# clocking.net
KiCad netlist of a schematic drawn in Altium Designer
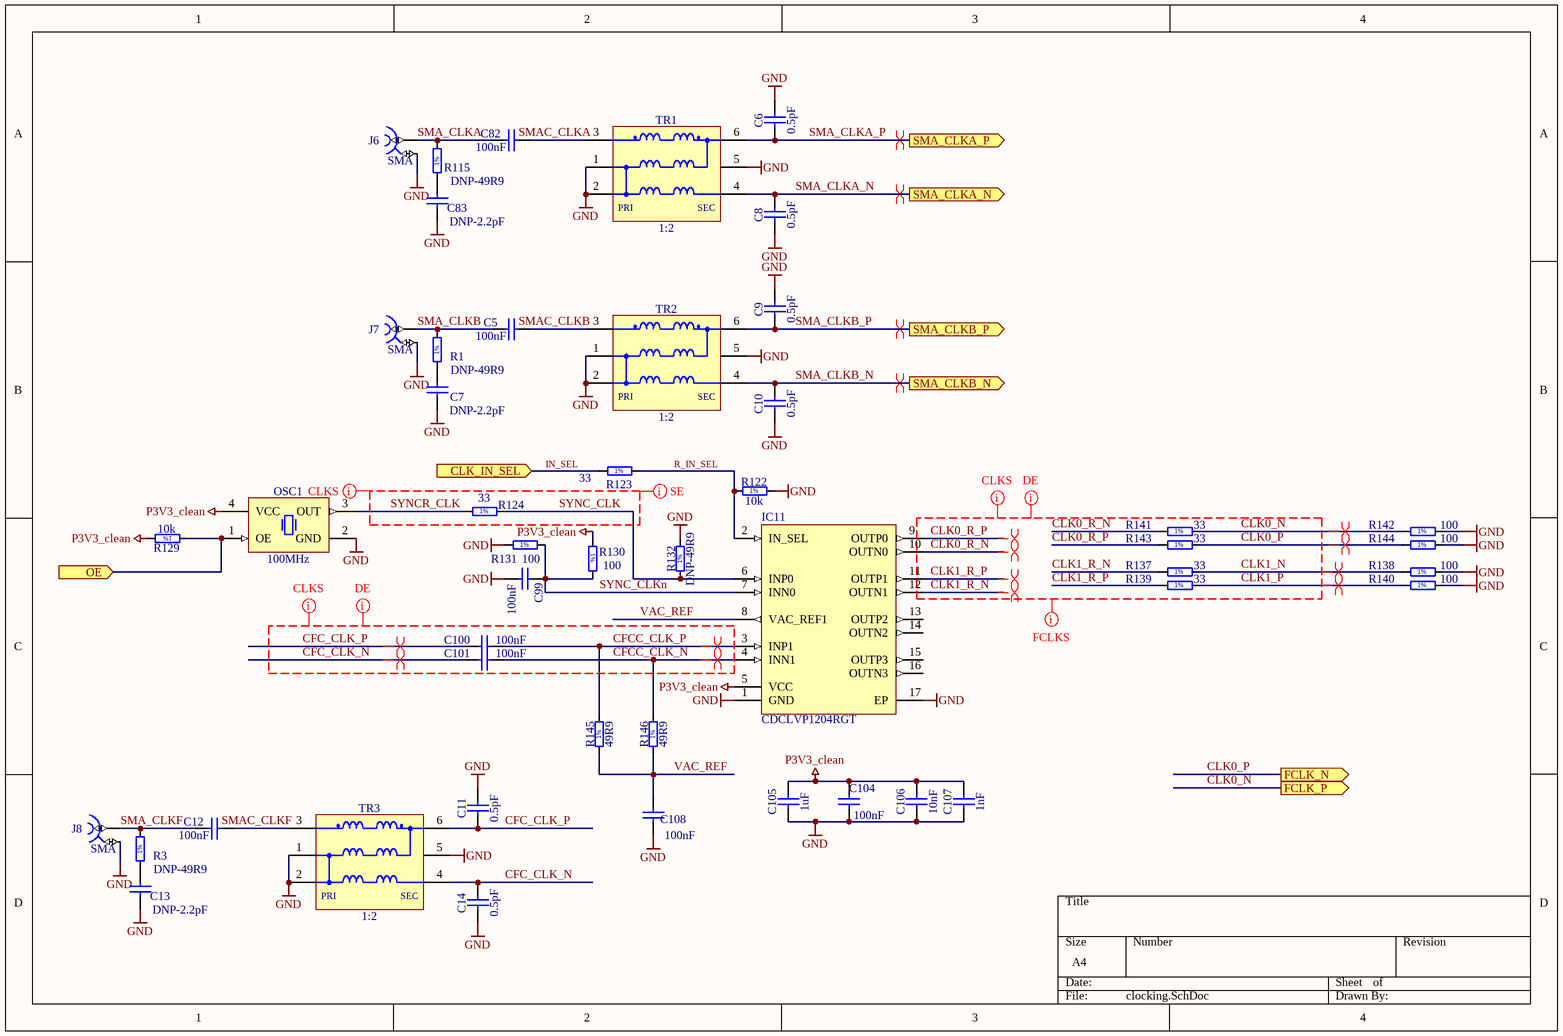
[diagram p0: clocking.SchDoc]

(export (version "E")
  (design (tool "Eeschema 10.0.6"))
  (components
    (comp (ref "C5")
      (value "100nF")
      (footprint "CAPC1005X55N")
      (description "Non-polarised capacitor")
      (fields
        (field (name "PART NUMBER") "CC0402_100NF_16V_10%_X5R")
        (field (name "VOLTAGE") "16V")
        (field (name "AUTHOR") "CERN DEM JLC")
      )
      (libsource (lib "Capacitors") (part "Capacitor - non polarized"))
    )
    (comp (ref "C6")
      (value "0.5pF")
      (footprint "CAPC1005X50N")
      (description "Non-polarised capacitor")
      (fields
        (field (name "PART NUMBER") "CC0402_0.5PF_25V_0.05PF_AVX_04023J0R5ABSTR")
        (field (name "VOLTAGE") "25V")
        (field (name "AUTHOR") "CERN DEM JLC")
      )
      (libsource (lib "Capacitors") (part "Capacitor - non polarized"))
    )
    (comp (ref "C7")
      (value "DNP-2.2pF")
      (footprint "CAPC1005X55N")
      (description "Non-polarised capacitor")
      (fields
        (field (name "PART NUMBER") "CC0402_2.2PF_50V_0.25PF_NP0")
        (field (name "VOLTAGE") "50V")
        (field (name "AUTHOR") "CERN DEM JLC")
      )
      (libsource (lib "Capacitors") (part "Capacitor - non polarized"))
    )
    (comp (ref "C8")
      (value "0.5pF")
      (footprint "CAPC1005X50N")
      (description "Non-polarised capacitor")
      (fields
        (field (name "PART NUMBER") "CC0402_0.5PF_25V_0.05PF_AVX_04023J0R5ABSTR")
        (field (name "VOLTAGE") "25V")
        (field (name "AUTHOR") "CERN DEM JLC")
      )
      (libsource (lib "Capacitors") (part "Capacitor - non polarized"))
    )
    (comp (ref "C9")
      (value "0.5pF")
      (footprint "CAPC1005X50N")
      (description "Non-polarised capacitor")
      (fields
        (field (name "PART NUMBER") "CC0402_0.5PF_25V_0.05PF_AVX_04023J0R5ABSTR")
        (field (name "VOLTAGE") "25V")
        (field (name "AUTHOR") "CERN DEM JLC")
      )
      (libsource (lib "Capacitors") (part "Capacitor - non polarized"))
    )
    (comp (ref "C10")
      (value "0.5pF")
      (footprint "CAPC1005X50N")
      (description "Non-polarised capacitor")
      (fields
        (field (name "PART NUMBER") "CC0402_0.5PF_25V_0.05PF_AVX_04023J0R5ABSTR")
        (field (name "VOLTAGE") "25V")
        (field (name "AUTHOR") "CERN DEM JLC")
      )
      (libsource (lib "Capacitors") (part "Capacitor - non polarized"))
    )
    (comp (ref "C11")
      (value "0.5pF")
      (footprint "CAPC1005X50N")
      (description "Non-polarised capacitor")
      (fields
        (field (name "PART NUMBER") "CC0402_0.5PF_25V_0.05PF_AVX_04023J0R5ABSTR")
        (field (name "VOLTAGE") "25V")
        (field (name "AUTHOR") "CERN DEM JLC")
      )
      (libsource (lib "Capacitors") (part "Capacitor - non polarized"))
    )
    (comp (ref "C12")
      (value "100nF")
      (footprint "CAPC1005X55N")
      (description "Non-polarised capacitor")
      (fields
        (field (name "PART NUMBER") "CC0402_100NF_16V_10%_X5R")
        (field (name "VOLTAGE") "16V")
        (field (name "AUTHOR") "CERN DEM JLC")
      )
      (libsource (lib "Capacitors") (part "Capacitor - non polarized"))
    )
    (comp (ref "C13")
      (value "DNP-2.2pF")
      (footprint "CAPC1005X55N")
      (description "Non-polarised capacitor")
      (fields
        (field (name "PART NUMBER") "CC0402_2.2PF_50V_0.25PF_NP0")
        (field (name "VOLTAGE") "50V")
        (field (name "AUTHOR") "CERN DEM JLC")
      )
      (libsource (lib "Capacitors") (part "Capacitor - non polarized"))
    )
    (comp (ref "C14")
      (value "0.5pF")
      (footprint "CAPC1005X50N")
      (description "Non-polarised capacitor")
      (fields
        (field (name "PART NUMBER") "CC0402_0.5PF_25V_0.05PF_AVX_04023J0R5ABSTR")
        (field (name "VOLTAGE") "25V")
        (field (name "AUTHOR") "CERN DEM JLC")
      )
      (libsource (lib "Capacitors") (part "Capacitor - non polarized"))
    )
    (comp (ref "C82")
      (value "100nF")
      (footprint "CAPC1005X55N")
      (description "Non-polarised capacitor")
      (fields
        (field (name "PART NUMBER") "CC0402_100NF_16V_10%_X5R")
        (field (name "VOLTAGE") "16V")
        (field (name "AUTHOR") "CERN DEM JLC")
      )
      (libsource (lib "Capacitors") (part "Capacitor - non polarized"))
    )
    (comp (ref "C83")
      (value "DNP-2.2pF")
      (footprint "CAPC1005X55N")
      (description "Non-polarised capacitor")
      (fields
        (field (name "PART NUMBER") "CC0402_2.2PF_50V_0.25PF_NP0")
        (field (name "VOLTAGE") "50V")
        (field (name "AUTHOR") "CERN DEM JLC")
      )
      (libsource (lib "Capacitors") (part "Capacitor - non polarized"))
    )
    (comp (ref "C99")
      (value "100nF")
      (footprint "CAPC0603X33N")
      (description "Non-polarised capacitor")
      (fields
        (field (name "PART NUMBER") "CC0201_100NF_6.3V_10%_X5R")
        (field (name "VOLTAGE") "6.3V")
        (field (name "AUTHOR") "CERN DEM JLC")
      )
      (libsource (lib "Capacitors") (part "Capacitor - non polarized"))
    )
    (comp (ref "C100")
      (value "100nF")
      (footprint "CAPC0603X33N")
      (description "Non-polarised capacitor")
      (fields
        (field (name "PART NUMBER") "CC0201_100NF_6.3V_10%_X5R")
        (field (name "VOLTAGE") "6.3V")
        (field (name "AUTHOR") "CERN DEM JLC")
      )
      (libsource (lib "Capacitors") (part "Capacitor - non polarized"))
    )
    (comp (ref "C101")
      (value "100nF")
      (footprint "CAPC0603X33N")
      (description "Non-polarised capacitor")
      (fields
        (field (name "PART NUMBER") "CC0201_100NF_6.3V_10%_X5R")
        (field (name "VOLTAGE") "6.3V")
        (field (name "AUTHOR") "CERN DEM JLC")
      )
      (libsource (lib "Capacitors") (part "Capacitor - non polarized"))
    )
    (comp (ref "C104")
      (value "100nF")
      (footprint "CAPC0603X33N")
      (description "Non-polarised capacitor")
      (fields
        (field (name "PART NUMBER") "CC0201_100NF_6.3V_10%_X5R")
        (field (name "VOLTAGE") "6.3V")
        (field (name "AUTHOR") "CERN DEM JLC")
      )
      (libsource (lib "Capacitors") (part "Capacitor - non polarized"))
    )
    (comp (ref "C105")
      (value "1uF")
      (footprint "CAPC1608X87N")
      (description "Non-polarised capacitor")
      (fields
        (field (name "PART NUMBER") "CC0603_1UF_25V_10%_X7R")
        (field (name "VOLTAGE") "25V")
        (field (name "AUTHOR") "CERN DEM JLC")
      )
      (libsource (lib "Capacitors") (part "Capacitor - non polarized"))
    )
    (comp (ref "C106")
      (value "10nF")
      (footprint "CAPC0603X33N")
      (description "Non-polarised capacitor")
      (fields
        (field (name "PART NUMBER") "CC0201_10NF_10V_10%_X5R")
        (field (name "VOLTAGE") "10V")
        (field (name "AUTHOR") "CERN DEM JLC")
      )
      (libsource (lib "Capacitors") (part "Capacitor - non polarized"))
    )
    (comp (ref "C107")
      (value "1nF")
      (footprint "CAPC0603X33N")
      (description "Non-polarised capacitor")
      (fields
        (field (name "PART NUMBER") "CC0201_1NF_16V_10%_X5R")
        (field (name "VOLTAGE") "16V")
        (field (name "AUTHOR") "CERN DEM JLC")
      )
      (libsource (lib "Capacitors") (part "Capacitor - non polarized"))
    )
    (comp (ref "C108")
      (value "100nF")
      (footprint "CAPC1005X55N")
      (description "Non-polarised capacitor")
      (fields
        (field (name "PART NUMBER") "CC0402_100NF_16V_10%_X5R")
        (field (name "VOLTAGE") "16V")
        (field (name "AUTHOR") "CERN DEM JLC")
      )
      (libsource (lib "Capacitors") (part "Capacitor - non polarized"))
    )
    (comp (ref "IC11")
      (value "CDCLVP1204RGT")
      (footprint "QFN50P300X300X100-17N-S165")
      (description "2:2 Low Additive Jitter LVPECL Buffer")
      (libsource (lib "TJ_LIB") (part "CDCLVP1204RGT"))
    )
    (comp (ref "J6")
      (value "SMA")
      (footprint "HUBER-SUHNER_85_SMA-50-0-101/111_NE")
      (fields
        (field (name "PART NUMBER") "HUBER-SUHNER_85_SMA-50-0-101/111_NE")
        (field (name "MANUFACTURER") "HUBER+SUHNER")
        (field (name "MANUFACTURER PART NUMBER") "85_SMA-50-0-101/111_NE")
        (field (name "AUTHOR") "CERN DEM JLC")
      )
      (libsource (lib "Connectors") (part "Coax_1Female_1Shield"))
    )
    (comp (ref "J7")
      (value "SMA")
      (footprint "HUBER-SUHNER_85_SMA-50-0-101/111_NE")
      (fields
        (field (name "PART NUMBER") "HUBER-SUHNER_85_SMA-50-0-101/111_NE")
        (field (name "MANUFACTURER") "HUBER+SUHNER")
        (field (name "MANUFACTURER PART NUMBER") "85_SMA-50-0-101/111_NE")
        (field (name "AUTHOR") "CERN DEM JLC")
      )
      (libsource (lib "Connectors") (part "Coax_1Female_1Shield"))
    )
    (comp (ref "J8")
      (value "SMA")
      (footprint "HUBER-SUHNER_85_SMA-50-0-101/111_NE")
      (fields
        (field (name "PART NUMBER") "HUBER-SUHNER_85_SMA-50-0-101/111_NE")
        (field (name "MANUFACTURER") "HUBER+SUHNER")
        (field (name "MANUFACTURER PART NUMBER") "85_SMA-50-0-101/111_NE")
        (field (name "AUTHOR") "CERN DEM JLC")
      )
      (libsource (lib "Connectors") (part "Coax_1Female_1Shield"))
    )
    (comp (ref "OSC1")
      (value "100MHz")
      (footprint "OSC_EPSON_SG-8002CA")
      (description "Oscillator 4 pins 1=OE 2=GND 3=OUT 4=VCC")
      (fields
        (field (name "PART NUMBER") "OSC_100MHZ_EPSON_SG-8002CAPCB100MHZ")
        (field (name "MANUFACTURER") "EPSON-TOYOCOM")
        (field (name "AUTHOR") "CERN DEM JLC")
      )
      (libsource (lib "ICs And Semiconductors") (part "Oscillator 1OE 2GND 3OUT 4VCC"))
    )
    (comp (ref "R1")
      (value "DNP-49R9")
      (footprint "RESC1005X40N")
      (description "Resistor - 1%")
      (fields
        (field (name "PART NUMBER") "R0402_49R9_1%_0.0625W_100PPM")
        (field (name "POWER") "0.0625W")
        (field (name "AUTHOR") "CERN DEM JLC")
      )
      (libsource (lib "Resistors") (part "Resistor - 1%"))
    )
    (comp (ref "R3")
      (value "DNP-49R9")
      (footprint "RESC1005X40N")
      (description "Resistor - 1%")
      (fields
        (field (name "PART NUMBER") "R0402_49R9_1%_0.0625W_100PPM")
        (field (name "POWER") "0.0625W")
        (field (name "AUTHOR") "CERN DEM JLC")
      )
      (libsource (lib "Resistors") (part "Resistor - 1%"))
    )
    (comp (ref "R115")
      (value "DNP-49R9")
      (footprint "RESC1005X40N")
      (description "Resistor - 1%")
      (fields
        (field (name "PART NUMBER") "R0402_49R9_1%_0.0625W_100PPM")
        (field (name "POWER") "0.0625W")
        (field (name "AUTHOR") "CERN DEM JLC")
      )
      (libsource (lib "Resistors") (part "Resistor - 1%"))
    )
    (comp (ref "R122")
      (value "10k")
      (footprint "RESC1005X40N")
      (description "Resistor - 1%")
      (fields
        (field (name "PART NUMBER") "R0402_10K_1%_0.0625W_100PPM")
        (field (name "POWER") "0.0625W")
        (field (name "AUTHOR") "CERN DEM JLC")
      )
      (libsource (lib "Resistors") (part "Resistor - 1%"))
    )
    (comp (ref "R123")
      (value "33")
      (footprint "RESC1005X40N")
      (description "Resistor - 1%")
      (fields
        (field (name "PART NUMBER") "R0402_33R_1%_0.0625W_100PPM")
        (field (name "POWER") "0.0625W")
        (field (name "AUTHOR") "CERN DEM JLC")
      )
      (libsource (lib "Resistors") (part "Resistor - 1%"))
    )
    (comp (ref "R124")
      (value "33")
      (footprint "RESC1005X40N")
      (description "Resistor - 1%")
      (fields
        (field (name "PART NUMBER") "R0402_33R_1%_0.0625W_100PPM")
        (field (name "POWER") "0.0625W")
        (field (name "AUTHOR") "CERN DEM JLC")
      )
      (libsource (lib "Resistors") (part "Resistor - 1%"))
    )
    (comp (ref "R129")
      (value "10k")
      (footprint "RESC1005X40N")
      (description "Resistor - 1%")
      (fields
        (field (name "PART NUMBER") "R0402_10K_1%_0.0625W_100PPM")
        (field (name "POWER") "0.0625W")
        (field (name "AUTHOR") "CERN DEM JLC")
      )
      (libsource (lib "Resistors") (part "Resistor - 1%"))
    )
    (comp (ref "R130")
      (value "100")
      (footprint "RESC1005X40N")
      (description "Resistor - 1%")
      (fields
        (field (name "PART NUMBER") "R0402_100R_1%_0.0625W_100PPM")
        (field (name "POWER") "0.0625W")
        (field (name "AUTHOR") "CERN DEM JLC")
      )
      (libsource (lib "Resistors") (part "Resistor - 1%"))
    )
    (comp (ref "R131")
      (value "100")
      (footprint "RESC1005X40N")
      (description "Resistor - 1%")
      (fields
        (field (name "PART NUMBER") "R0402_100R_1%_0.0625W_100PPM")
        (field (name "POWER") "0.0625W")
        (field (name "AUTHOR") "CERN DEM JLC")
      )
      (libsource (lib "Resistors") (part "Resistor - 1%"))
    )
    (comp (ref "R132")
      (value "DNP-49R9")
      (footprint "RESC1005X40N")
      (description "Resistor - 1%")
      (fields
        (field (name "PART NUMBER") "R0402_49R9_1%_0.0625W_100PPM")
        (field (name "POWER") "0.0625W")
        (field (name "AUTHOR") "CERN DEM JLC")
      )
      (libsource (lib "Resistors") (part "Resistor - 1%"))
    )
    (comp (ref "R137")
      (value "33")
      (footprint "RESC1005X40N")
      (description "Resistor - 1%")
      (fields
        (field (name "PART NUMBER") "R0402_33R_1%_0.0625W_100PPM")
        (field (name "POWER") "0.0625W")
        (field (name "AUTHOR") "CERN DEM JLC")
      )
      (libsource (lib "Resistors") (part "Resistor - 1%"))
    )
    (comp (ref "R138")
      (value "100")
      (footprint "RESC1005X40N")
      (description "Resistor - 1%")
      (fields
        (field (name "PART NUMBER") "R0402_100R_1%_0.0625W_100PPM")
        (field (name "POWER") "0.0625W")
        (field (name "AUTHOR") "CERN DEM JLC")
      )
      (libsource (lib "Resistors") (part "Resistor - 1%"))
    )
    (comp (ref "R139")
      (value "33")
      (footprint "RESC1005X40N")
      (description "Resistor - 1%")
      (fields
        (field (name "PART NUMBER") "R0402_33R_1%_0.0625W_100PPM")
        (field (name "POWER") "0.0625W")
        (field (name "AUTHOR") "CERN DEM JLC")
      )
      (libsource (lib "Resistors") (part "Resistor - 1%"))
    )
    (comp (ref "R140")
      (value "100")
      (footprint "RESC1005X40N")
      (description "Resistor - 1%")
      (fields
        (field (name "PART NUMBER") "R0402_100R_1%_0.0625W_100PPM")
        (field (name "POWER") "0.0625W")
        (field (name "AUTHOR") "CERN DEM JLC")
      )
      (libsource (lib "Resistors") (part "Resistor - 1%"))
    )
    (comp (ref "R141")
      (value "33")
      (footprint "RESC1005X40N")
      (description "Resistor - 1%")
      (fields
        (field (name "PART NUMBER") "R0402_33R_1%_0.0625W_100PPM")
        (field (name "POWER") "0.0625W")
        (field (name "AUTHOR") "CERN DEM JLC")
      )
      (libsource (lib "Resistors") (part "Resistor - 1%"))
    )
    (comp (ref "R142")
      (value "100")
      (footprint "RESC1005X40N")
      (description "Resistor - 1%")
      (fields
        (field (name "PART NUMBER") "R0402_100R_1%_0.0625W_100PPM")
        (field (name "POWER") "0.0625W")
        (field (name "AUTHOR") "CERN DEM JLC")
      )
      (libsource (lib "Resistors") (part "Resistor - 1%"))
    )
    (comp (ref "R143")
      (value "33")
      (footprint "RESC1005X40N")
      (description "Resistor - 1%")
      (fields
        (field (name "PART NUMBER") "R0402_33R_1%_0.0625W_100PPM")
        (field (name "POWER") "0.0625W")
        (field (name "AUTHOR") "CERN DEM JLC")
      )
      (libsource (lib "Resistors") (part "Resistor - 1%"))
    )
    (comp (ref "R144")
      (value "100")
      (footprint "RESC1005X40N")
      (description "Resistor - 1%")
      (fields
        (field (name "PART NUMBER") "R0402_100R_1%_0.0625W_100PPM")
        (field (name "POWER") "0.0625W")
        (field (name "AUTHOR") "CERN DEM JLC")
      )
      (libsource (lib "Resistors") (part "Resistor - 1%"))
    )
    (comp (ref "R145")
      (value "49R9")
      (footprint "RESC1005X40N")
      (description "Resistor - 1%")
      (fields
        (field (name "PART NUMBER") "R0402_49R9_1%_0.0625W_100PPM")
        (field (name "POWER") "0.0625W")
        (field (name "AUTHOR") "CERN DEM JLC")
      )
      (libsource (lib "Resistors") (part "Resistor - 1%"))
    )
    (comp (ref "R146")
      (value "49R9")
      (footprint "RESC1005X40N")
      (description "Resistor - 1%")
      (fields
        (field (name "PART NUMBER") "R0402_49R9_1%_0.0625W_100PPM")
        (field (name "POWER") "0.0625W")
        (field (name "AUTHOR") "CERN DEM JLC")
      )
      (libsource (lib "Resistors") (part "Resistor - 1%"))
    )
    (comp (ref "TR1")
      (value "1:2")
      (footprint "XFMR_MINI-CIRCUITS_DB1627")
      (description "50 OHMS 10 to 4000 MHz RF Transformer")
      (fields
        (field (name "PART NUMBER") "XFMR_MINI-CIRCUITS_TCM2-43X+")
        (field (name "POWER") "0.4W")
        (field (name "AUTHOR") "CERN DEM BC")
      )
      (libsource (lib "Inductors & Transformers") (part "XFMR_MINI-CIRCUITS_TCM2-43X"))
    )
    (comp (ref "TR2")
      (value "1:2")
      (footprint "XFMR_MINI-CIRCUITS_DB1627")
      (description "50 OHMS 10 to 4000 MHz RF Transformer")
      (fields
        (field (name "PART NUMBER") "XFMR_MINI-CIRCUITS_TCM2-43X+")
        (field (name "POWER") "0.4W")
        (field (name "AUTHOR") "CERN DEM BC")
      )
      (libsource (lib "Inductors & Transformers") (part "XFMR_MINI-CIRCUITS_TCM2-43X"))
    )
    (comp (ref "TR3")
      (value "1:2")
      (footprint "XFMR_MINI-CIRCUITS_DB1627")
      (description "50 OHMS 10 to 4000 MHz RF Transformer")
      (fields
        (field (name "PART NUMBER") "XFMR_MINI-CIRCUITS_TCM2-43X+")
        (field (name "POWER") "0.4W")
        (field (name "AUTHOR") "CERN DEM BC")
      )
      (libsource (lib "Inductors & Transformers") (part "XFMR_MINI-CIRCUITS_TCM2-43X"))
    )
  )
  (nets
    (net (code "1") (name "/CFCC_CLK_N") (class "Default")
      (node (ref "C101") (pin "1") (pinfunction "1_1") (pintype "passive"))
      (node (ref "IC11") (pin "4") (pinfunction "INN1_4") (pintype "input"))
      (node (ref "R146") (pin "2") (pinfunction "2_2") (pintype "passive"))
    )
    (net (code "2") (name "/CFCC_CLK_P") (class "Default")
      (node (ref "C100") (pin "1") (pinfunction "1_1") (pintype "passive"))
      (node (ref "IC11") (pin "3") (pinfunction "INP1_3") (pintype "input"))
      (node (ref "R145") (pin "2") (pinfunction "2_2") (pintype "passive"))
    )
    (net (code "3") (name "/CFC_CLK_N") (class "Default")
      (node (ref "C101") (pin "2") (pinfunction "2_2") (pintype "passive"))
      (node (ref "C14") (pin "2") (pinfunction "2_2") (pintype "passive"))
      (node (ref "TR3") (pin "4") (pinfunction "S1_4") (pintype "passive"))
    )
    (net (code "4") (name "/CFC_CLK_P") (class "Default")
      (node (ref "C100") (pin "2") (pinfunction "2_2") (pintype "passive"))
      (node (ref "C11") (pin "1") (pinfunction "1_1") (pintype "passive"))
      (node (ref "TR3") (pin "6") (pinfunction "S1_6") (pintype "passive"))
    )
    (net (code "5") (name "/CLK0_N") (class "Default")
      (node (ref "R141") (pin "2") (pinfunction "2_2") (pintype "passive"))
      (node (ref "R142") (pin "1") (pinfunction "1_1") (pintype "passive"))
    )
    (net (code "6") (name "/CLK0_P") (class "Default")
      (node (ref "R143") (pin "2") (pinfunction "2_2") (pintype "passive"))
      (node (ref "R144") (pin "1") (pinfunction "1_1") (pintype "passive"))
    )
    (net (code "7") (name "/CLK0_R_N") (class "Default")
      (node (ref "IC11") (pin "10") (pinfunction "OUTN0_10") (pintype "output"))
      (node (ref "R141") (pin "1") (pinfunction "1_1") (pintype "passive"))
    )
    (net (code "8") (name "/CLK0_R_P") (class "Default")
      (node (ref "IC11") (pin "9") (pinfunction "OUTP0_9") (pintype "output"))
      (node (ref "R143") (pin "1") (pinfunction "1_1") (pintype "passive"))
    )
    (net (code "9") (name "/CLK1_N") (class "Default")
      (node (ref "R137") (pin "2") (pinfunction "2_2") (pintype "passive"))
      (node (ref "R138") (pin "1") (pinfunction "1_1") (pintype "passive"))
    )
    (net (code "10") (name "/CLK1_P") (class "Default")
      (node (ref "R139") (pin "2") (pinfunction "2_2") (pintype "passive"))
      (node (ref "R140") (pin "1") (pinfunction "1_1") (pintype "passive"))
    )
    (net (code "11") (name "/CLK1_R_N") (class "Default")
      (node (ref "IC11") (pin "12") (pinfunction "OUTN1_12") (pintype "output"))
      (node (ref "R137") (pin "1") (pinfunction "1_1") (pintype "passive"))
    )
    (net (code "12") (name "/CLK1_R_P") (class "Default")
      (node (ref "IC11") (pin "11") (pinfunction "OUTP1_11") (pintype "output"))
      (node (ref "R139") (pin "1") (pinfunction "1_1") (pintype "passive"))
    )
    (net (code "13") (name "/IN_SEL") (class "Default")
      (node (ref "R123") (pin "1") (pinfunction "1_1") (pintype "passive"))
    )
    (net (code "14") (name "/OE") (class "Default")
      (node (ref "OSC1") (pin "1") (pinfunction "OE_1") (pintype "input"))
      (node (ref "R129") (pin "1") (pinfunction "1_1") (pintype "passive"))
    )
    (net (code "15") (name "/R_IN_SEL") (class "Default")
      (node (ref "IC11") (pin "2") (pinfunction "IN_SEL_2") (pintype "input"))
      (node (ref "R122") (pin "1") (pinfunction "1_1") (pintype "passive"))
      (node (ref "R123") (pin "2") (pinfunction "2_2") (pintype "passive"))
    )
    (net (code "19") (name "/SMA_CLKA") (class "Default")
      (node (ref "C82") (pin "2") (pinfunction "2_2") (pintype "passive"))
      (node (ref "J6") (pin "1") (pinfunction "1_1") (pintype "bidirectional"))
      (node (ref "R115") (pin "2") (pinfunction "2_2") (pintype "passive"))
    )
    (net (code "20") (name "/SMA_CLKA_N") (class "Default")
      (node (ref "C8") (pin "2") (pinfunction "2_2") (pintype "passive"))
      (node (ref "TR1") (pin "4") (pinfunction "S1_4") (pintype "passive"))
    )
    (net (code "21") (name "/SMA_CLKA_P") (class "Default")
      (node (ref "C6") (pin "1") (pinfunction "1_1") (pintype "passive"))
      (node (ref "TR1") (pin "6") (pinfunction "S1_6") (pintype "passive"))
    )
    (net (code "22") (name "/SMA_CLKB") (class "Default")
      (node (ref "C5") (pin "2") (pinfunction "2_2") (pintype "passive"))
      (node (ref "J7") (pin "1") (pinfunction "1_1") (pintype "bidirectional"))
      (node (ref "R1") (pin "2") (pinfunction "2_2") (pintype "passive"))
    )
    (net (code "23") (name "/SMA_CLKB_N") (class "Default")
      (node (ref "C10") (pin "2") (pinfunction "2_2") (pintype "passive"))
      (node (ref "TR2") (pin "4") (pinfunction "S1_4") (pintype "passive"))
    )
    (net (code "24") (name "/SMA_CLKB_P") (class "Default")
      (node (ref "C9") (pin "1") (pinfunction "1_1") (pintype "passive"))
      (node (ref "TR2") (pin "6") (pinfunction "S1_6") (pintype "passive"))
    )
    (net (code "25") (name "/SMA_CLKF") (class "Default")
      (node (ref "C12") (pin "2") (pinfunction "2_2") (pintype "passive"))
      (node (ref "J8") (pin "1") (pinfunction "1_1") (pintype "bidirectional"))
      (node (ref "R3") (pin "2") (pinfunction "2_2") (pintype "passive"))
    )
    (net (code "26") (name "/SYNCR_CLK") (class "Default")
      (node (ref "OSC1") (pin "3") (pinfunction "OUT_3") (pintype "output"))
      (node (ref "R124") (pin "1") (pinfunction "1_1") (pintype "passive"))
    )
    (net (code "27") (name "/SYNC_CLK") (class "Default")
      (node (ref "IC11") (pin "6") (pinfunction "INP0_6") (pintype "input"))
      (node (ref "R124") (pin "2") (pinfunction "2_2") (pintype "passive"))
      (node (ref "R132") (pin "1") (pinfunction "1_1") (pintype "passive"))
    )
    (net (code "28") (name "/SYNC_CLKn") (class "Default")
      (node (ref "C99") (pin "2") (pinfunction "2_2") (pintype "passive"))
      (node (ref "IC11") (pin "7") (pinfunction "INN0_7") (pintype "input"))
      (node (ref "R130") (pin "2") (pinfunction "2_2") (pintype "passive"))
      (node (ref "R131") (pin "2") (pinfunction "2_2") (pintype "passive"))
    )
    (net (code "29") (name "/VAC_REF") (class "Default")
      (node (ref "C108") (pin "2") (pinfunction "2_2") (pintype "passive"))
      (node (ref "IC11") (pin "8") (pinfunction "VAC_REF1_8") (pintype "output"))
      (node (ref "R145") (pin "1") (pinfunction "1_1") (pintype "passive"))
      (node (ref "R146") (pin "1") (pinfunction "1_1") (pintype "passive"))
    )
    (net (code "30") (name "GND") (class "Default")
      (node (ref "C10") (pin "1") (pinfunction "1_1") (pintype "passive"))
      (node (ref "C104") (pin "1") (pinfunction "1_1") (pintype "passive"))
      (node (ref "C105") (pin "1") (pinfunction "1_1") (pintype "passive"))
      (node (ref "C106") (pin "1") (pinfunction "1_1") (pintype "passive"))
      (node (ref "C107") (pin "1") (pinfunction "1_1") (pintype "passive"))
      (node (ref "C108") (pin "1") (pinfunction "1_1") (pintype "passive"))
      (node (ref "C11") (pin "2") (pinfunction "2_2") (pintype "passive"))
      (node (ref "C13") (pin "2") (pinfunction "2_2") (pintype "passive"))
      (node (ref "C14") (pin "1") (pinfunction "1_1") (pintype "passive"))
      (node (ref "C6") (pin "2") (pinfunction "2_2") (pintype "passive"))
      (node (ref "C7") (pin "2") (pinfunction "2_2") (pintype "passive"))
      (node (ref "C8") (pin "1") (pinfunction "1_1") (pintype "passive"))
      (node (ref "C83") (pin "2") (pinfunction "2_2") (pintype "passive"))
      (node (ref "C9") (pin "2") (pinfunction "2_2") (pintype "passive"))
      (node (ref "C99") (pin "1") (pinfunction "1_1") (pintype "passive"))
      (node (ref "IC11") (pin "1") (pinfunction "GND_1") (pintype "power_in"))
      (node (ref "IC11") (pin "17") (pinfunction "EP_17") (pintype "power_in"))
      (node (ref "J6") (pin "2") (pinfunction "2_2") (pintype "bidirectional"))
      (node (ref "J7") (pin "2") (pinfunction "2_2") (pintype "bidirectional"))
      (node (ref "J8") (pin "2") (pinfunction "2_2") (pintype "bidirectional"))
      (node (ref "OSC1") (pin "2") (pinfunction "GND_2") (pintype "power_in"))
      (node (ref "R122") (pin "2") (pinfunction "2_2") (pintype "passive"))
      (node (ref "R131") (pin "1") (pinfunction "1_1") (pintype "passive"))
      (node (ref "R132") (pin "2") (pinfunction "2_2") (pintype "passive"))
      (node (ref "R138") (pin "2") (pinfunction "2_2") (pintype "passive"))
      (node (ref "R140") (pin "2") (pinfunction "2_2") (pintype "passive"))
      (node (ref "R142") (pin "2") (pinfunction "2_2") (pintype "passive"))
      (node (ref "R144") (pin "2") (pinfunction "2_2") (pintype "passive"))
      (node (ref "TR1") (pin "1") (pinfunction "P1_1") (pintype "passive"))
      (node (ref "TR1") (pin "2") (pinfunction "P1_2") (pintype "passive"))
      (node (ref "TR1") (pin "5") (pinfunction "NC_5") (pintype "passive"))
      (node (ref "TR2") (pin "1") (pinfunction "P1_1") (pintype "passive"))
      (node (ref "TR2") (pin "2") (pinfunction "P1_2") (pintype "passive"))
      (node (ref "TR2") (pin "5") (pinfunction "NC_5") (pintype "passive"))
      (node (ref "TR3") (pin "1") (pinfunction "P1_1") (pintype "passive"))
      (node (ref "TR3") (pin "2") (pinfunction "P1_2") (pintype "passive"))
      (node (ref "TR3") (pin "5") (pinfunction "NC_5") (pintype "passive"))
    )
    (net (code "31") (name "Net-(C5-Pad1)") (class "Default")
      (node (ref "C5") (pin "1") (pinfunction "1_1") (pintype "passive"))
      (node (ref "TR2") (pin "3") (pinfunction "P1_3") (pintype "passive"))
    )
    (net (code "32") (name "Net-(C7-Pad1)") (class "Default")
      (node (ref "C7") (pin "1") (pinfunction "1_1") (pintype "passive"))
      (node (ref "R1") (pin "1") (pinfunction "1_1") (pintype "passive"))
    )
    (net (code "33") (name "Net-(C12-Pad1)") (class "Default")
      (node (ref "C12") (pin "1") (pinfunction "1_1") (pintype "passive"))
      (node (ref "TR3") (pin "3") (pinfunction "P1_3") (pintype "passive"))
    )
    (net (code "34") (name "Net-(C13-Pad1)") (class "Default")
      (node (ref "C13") (pin "1") (pinfunction "1_1") (pintype "passive"))
      (node (ref "R3") (pin "1") (pinfunction "1_1") (pintype "passive"))
    )
    (net (code "35") (name "Net-(C82-Pad1)") (class "Default")
      (node (ref "C82") (pin "1") (pinfunction "1_1") (pintype "passive"))
      (node (ref "TR1") (pin "3") (pinfunction "P1_3") (pintype "passive"))
    )
    (net (code "36") (name "Net-(C83-Pad1)") (class "Default")
      (node (ref "C83") (pin "1") (pinfunction "1_1") (pintype "passive"))
      (node (ref "R115") (pin "1") (pinfunction "1_1") (pintype "passive"))
    )
    (net (code "37") (name "P3V3_clean") (class "Default")
      (node (ref "C104") (pin "2") (pinfunction "2_2") (pintype "passive"))
      (node (ref "C105") (pin "2") (pinfunction "2_2") (pintype "passive"))
      (node (ref "C106") (pin "2") (pinfunction "2_2") (pintype "passive"))
      (node (ref "C107") (pin "2") (pinfunction "2_2") (pintype "passive"))
      (node (ref "IC11") (pin "5") (pinfunction "VCC_5") (pintype "power_in"))
      (node (ref "OSC1") (pin "4") (pinfunction "VCC_4") (pintype "power_in"))
      (node (ref "R129") (pin "2") (pinfunction "2_2") (pintype "passive"))
      (node (ref "R130") (pin "1") (pinfunction "1_1") (pintype "passive"))
    )
    (net (code "38") (name "unconnected-(IC11-OUTN2-Pad14)") (class "Default")
      (node (ref "IC11") (pin "14") (pinfunction "OUTN2_14") (pintype "output"))
    )
    (net (code "39") (name "unconnected-(IC11-OUTN3-Pad16)") (class "Default")
      (node (ref "IC11") (pin "16") (pinfunction "OUTN3_16") (pintype "output"))
    )
    (net (code "40") (name "unconnected-(IC11-OUTP2-Pad13)") (class "Default")
      (node (ref "IC11") (pin "13") (pinfunction "OUTP2_13") (pintype "output"))
    )
    (net (code "41") (name "unconnected-(IC11-OUTP3-Pad15)") (class "Default")
      (node (ref "IC11") (pin "15") (pinfunction "OUTP3_15") (pintype "output"))
    )
  )
)
